# ccd_driver.net
KiCad netlist of a schematic drawn in EAGLE
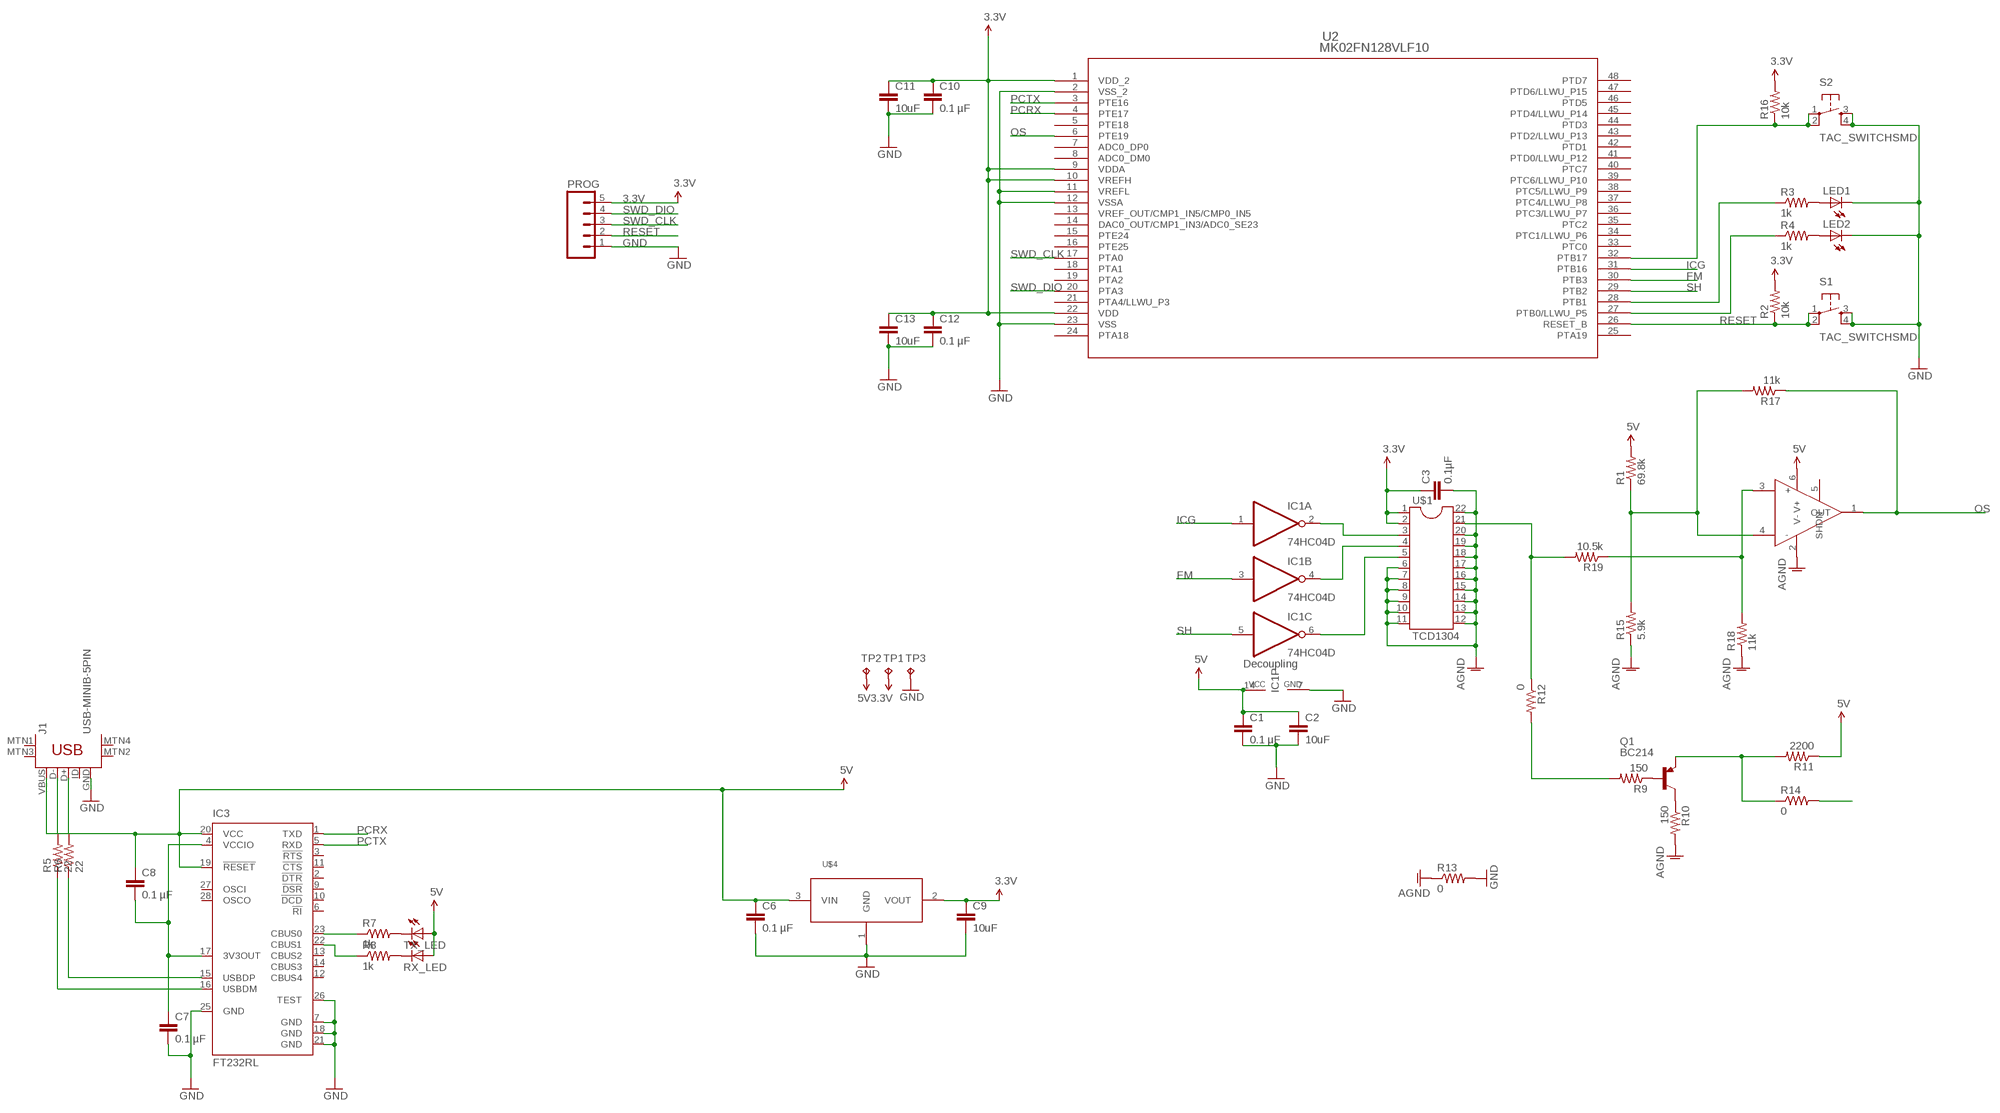
[diagram p0: schematic, sheet 1]

(export (version "E")
  (design (tool "Eeschema 10.0.6"))
  (components
    (comp (ref "C1")
      (value "0.1 µF")
      (footprint "eagle-import:C1206")
      (libsource (lib "eagle-import") (part "C-EUC1206"))
    )
    (comp (ref "C2")
      (value "10uF")
      (footprint "eagle-import:C1206")
      (libsource (lib "eagle-import") (part "C-EUC1206"))
    )
    (comp (ref "C3")
      (value "0.1µF")
      (footprint "eagle-import:C1206")
      (libsource (lib "eagle-import") (part "C-EUC1206"))
    )
    (comp (ref "C6")
      (value "0.1 µF")
      (footprint "eagle-import:C1206")
      (libsource (lib "eagle-import") (part "C-EUC1206"))
    )
    (comp (ref "C7")
      (value "0.1 µF")
      (footprint "eagle-import:C1206")
      (libsource (lib "eagle-import") (part "C-EUC1206"))
    )
    (comp (ref "C8")
      (value "0.1 µF")
      (footprint "eagle-import:C1206")
      (libsource (lib "eagle-import") (part "C-EUC1206"))
    )
    (comp (ref "C9")
      (value "10uF")
      (footprint "eagle-import:C1206")
      (libsource (lib "eagle-import") (part "C-EUC1206"))
    )
    (comp (ref "C10")
      (value "0.1 µF")
      (footprint "eagle-import:C1206")
      (libsource (lib "eagle-import") (part "C-EUC1206"))
    )
    (comp (ref "C11")
      (value "10uF")
      (footprint "eagle-import:C1206")
      (libsource (lib "eagle-import") (part "C-EUC1206"))
    )
    (comp (ref "C12")
      (value "0.1 µF")
      (footprint "eagle-import:C1206")
      (libsource (lib "eagle-import") (part "C-EUC1206"))
    )
    (comp (ref "C13")
      (value "10uF")
      (footprint "eagle-import:C1206")
      (libsource (lib "eagle-import") (part "C-EUC1206"))
    )
    (comp (ref "IC1")
      (value "74HC04D")
      (footprint "eagle-import:SO14")
      (libsource (lib "eagle-import") (part "7404DHC"))
    )
    (comp (ref "IC3")
      (value "FT232RL")
      (footprint "eagle-import:SSOP28")
      (libsource (lib "eagle-import") (part "FT232RL"))
    )
    (comp (ref "J1")
      (value "USB-MINIB-5PIN")
      (footprint "eagle-import:USB-MINIB")
      (libsource (lib "eagle-import") (part "USB-MINIB-5PIN"))
    )
    (comp (ref "LED1")
      (value "LEDCHIPLED_0805")
      (footprint "eagle-import:CHIPLED_0805")
      (libsource (lib "eagle-import") (part "LEDCHIPLED_0805"))
    )
    (comp (ref "LED2")
      (value "LEDCHIPLED_0805")
      (footprint "eagle-import:CHIPLED_0805")
      (libsource (lib "eagle-import") (part "LEDCHIPLED_0805"))
    )
    (comp (ref "PROG")
      (value "M05LOCK")
      (footprint "eagle-import:1X05_LOCK")
      (libsource (lib "eagle-import") (part "M05LOCK"))
    )
    (comp (ref "Q1")
      (value "BC214")
      (footprint "eagle-import:TO92")
      (libsource (lib "eagle-import") (part "BC214"))
    )
    (comp (ref "R1")
      (value "69.8k")
      (footprint "eagle-import:R0805")
      (libsource (lib "eagle-import") (part "R-US_R0805"))
    )
    (comp (ref "R2")
      (value "10k")
      (footprint "eagle-import:R0805")
      (libsource (lib "eagle-import") (part "R-US_R0805"))
    )
    (comp (ref "R3")
      (value "1k")
      (footprint "eagle-import:R0805")
      (libsource (lib "eagle-import") (part "R-US_R0805"))
    )
    (comp (ref "R4")
      (value "1k")
      (footprint "eagle-import:R0805")
      (libsource (lib "eagle-import") (part "R-US_R0805"))
    )
    (comp (ref "R5")
      (value "22")
      (footprint "eagle-import:R0805")
      (libsource (lib "eagle-import") (part "R-US_R0805"))
    )
    (comp (ref "R6")
      (value "22")
      (footprint "eagle-import:R0805")
      (libsource (lib "eagle-import") (part "R-US_R0805"))
    )
    (comp (ref "R7")
      (value "1k")
      (footprint "eagle-import:R0805")
      (libsource (lib "eagle-import") (part "R-US_R0805"))
    )
    (comp (ref "R8")
      (value "1k")
      (footprint "eagle-import:R0805")
      (libsource (lib "eagle-import") (part "R-US_R0805"))
    )
    (comp (ref "R9")
      (value "150")
      (footprint "eagle-import:R0805")
      (libsource (lib "eagle-import") (part "R-US_R0805"))
    )
    (comp (ref "R10")
      (value "150")
      (footprint "eagle-import:R0805")
      (libsource (lib "eagle-import") (part "R-US_R0805"))
    )
    (comp (ref "R11")
      (value "2200")
      (footprint "eagle-import:R0805")
      (libsource (lib "eagle-import") (part "R-US_R0805"))
    )
    (comp (ref "R12")
      (value "0")
      (footprint "eagle-import:R0805")
      (libsource (lib "eagle-import") (part "R-US_R0805"))
    )
    (comp (ref "R13")
      (value "0")
      (footprint "eagle-import:R0805")
      (libsource (lib "eagle-import") (part "R-US_R0805"))
    )
    (comp (ref "R14")
      (value "0")
      (footprint "eagle-import:R0805")
      (libsource (lib "eagle-import") (part "R-US_R0805"))
    )
    (comp (ref "R15")
      (value "5.9k")
      (footprint "eagle-import:R0805")
      (libsource (lib "eagle-import") (part "R-US_R0805"))
    )
    (comp (ref "R16")
      (value "10k")
      (footprint "eagle-import:R0805")
      (libsource (lib "eagle-import") (part "R-US_R0805"))
    )
    (comp (ref "R17")
      (value "11k")
      (footprint "eagle-import:R0805")
      (libsource (lib "eagle-import") (part "R-US_R0805"))
    )
    (comp (ref "R18")
      (value "11k")
      (footprint "eagle-import:R0805")
      (libsource (lib "eagle-import") (part "R-US_R0805"))
    )
    (comp (ref "R19")
      (value "10.5k")
      (footprint "eagle-import:R0805")
      (libsource (lib "eagle-import") (part "R-US_R0805"))
    )
    (comp (ref "RX_LED")
      (value "LEDCHIPLED_0805")
      (footprint "eagle-import:CHIPLED_0805")
      (libsource (lib "eagle-import") (part "LEDCHIPLED_0805"))
    )
    (comp (ref "S1")
      (value "TAC_SWITCHSMD")
      (footprint "eagle-import:TACTILE-SWITCH-SMD")
      (libsource (lib "eagle-import") (part "TAC_SWITCHSMD"))
    )
    (comp (ref "S2")
      (value "TAC_SWITCHSMD")
      (footprint "eagle-import:TACTILE-SWITCH-SMD")
      (libsource (lib "eagle-import") (part "TAC_SWITCHSMD"))
    )
    (comp (ref "TP1")
      (value "TPPAD1-17Y")
      (footprint "eagle-import:P1-17Y")
      (libsource (lib "eagle-import") (part "TPPAD1-17Y"))
    )
    (comp (ref "TP2")
      (value "TPPAD1-17Y")
      (footprint "eagle-import:P1-17Y")
      (libsource (lib "eagle-import") (part "TPPAD1-17Y"))
    )
    (comp (ref "TP3")
      (value "TPPAD1-17Y")
      (footprint "eagle-import:P1-17Y")
      (libsource (lib "eagle-import") (part "TPPAD1-17Y"))
    )
    (comp (ref "TX_LED")
      (value "LEDCHIPLED_0805")
      (footprint "eagle-import:CHIPLED_0805")
      (libsource (lib "eagle-import") (part "LEDCHIPLED_0805"))
    )
    (comp (ref "U$1")
      (value "TCD1304")
      (footprint "eagle-import:TCD1304")
      (libsource (lib "eagle-import") (part "TCD1304"))
    )
    (comp (ref "U$3")
      (value "LTC6252")
      (footprint "eagle-import:TSOT23-6")
      (libsource (lib "eagle-import") (part "LTC6252"))
    )
    (comp (ref "U$4")
      (value "LD1117V33")
      (footprint "eagle-import:TO220H")
      (libsource (lib "eagle-import") (part "LD1117V33"))
    )
    (comp (ref "U2")
      (value "MK02FN128VLF10")
      (footprint "eagle-import:LQFP-48_7X7X1.6")
      (fields (field (name "MANUFACTURER_PART_NUMBER") "mk02fn128vlf10"))
      (libsource (lib "eagle-import") (part "MK02FN128VLF10"))
    )
  )
  (nets
    (net (code "1") (name "/FM") (class "Default")
      (node (ref "IC1") (pin "3") (pinfunction "I_3") (pintype "input"))
      (node (ref "U2") (pin "30") (pinfunction "PTB3_30") (pintype "bidirectional"))
    )
    (net (code "2") (name "/ICG") (class "Default")
      (node (ref "IC1") (pin "1") (pinfunction "I_1") (pintype "input"))
      (node (ref "U2") (pin "31") (pinfunction "PTB16_31") (pintype "bidirectional"))
    )
    (net (code "3") (name "/OS") (class "Default")
      (node (ref "R14") (pin "2") (pinfunction "2_2") (pintype "passive"))
      (node (ref "R17") (pin "1") (pinfunction "1_1") (pintype "passive"))
      (node (ref "U$3") (pin "1") (pinfunction "OUT_1") (pintype "bidirectional"))
      (node (ref "U2") (pin "6") (pinfunction "PTE19_6") (pintype "bidirectional"))
    )
    (net (code "4") (name "/PCRX") (class "Default")
      (node (ref "IC3") (pin "1") (pinfunction "TXD_1") (pintype "output"))
      (node (ref "U2") (pin "4") (pinfunction "PTE17_4") (pintype "bidirectional"))
    )
    (net (code "5") (name "/PCTX") (class "Default")
      (node (ref "IC3") (pin "5") (pinfunction "RXD_5") (pintype "input"))
      (node (ref "U2") (pin "3") (pinfunction "PTE16_3") (pintype "bidirectional"))
    )
    (net (code "6") (name "/RESET") (class "Default")
      (node (ref "PROG") (pin "2") (pinfunction "2_2") (pintype "passive"))
      (node (ref "R2") (pin "1") (pinfunction "1_1") (pintype "passive"))
      (node (ref "S1") (pin "1") (pinfunction "1_1") (pintype "passive"))
      (node (ref "S1") (pin "2") (pinfunction "2_2") (pintype "passive"))
      (node (ref "U2") (pin "26") (pinfunction "RESET_B_26") (pintype "passive"))
    )
    (net (code "7") (name "/SH") (class "Default")
      (node (ref "IC1") (pin "5") (pinfunction "I_5") (pintype "input"))
      (node (ref "U2") (pin "29") (pinfunction "PTB2_29") (pintype "bidirectional"))
    )
    (net (code "8") (name "/SWD_CLK") (class "Default")
      (node (ref "PROG") (pin "3") (pinfunction "3_3") (pintype "passive"))
      (node (ref "U2") (pin "17") (pinfunction "PTA0_17") (pintype "bidirectional"))
    )
    (net (code "9") (name "/SWD_DIO") (class "Default")
      (node (ref "PROG") (pin "4") (pinfunction "4_4") (pintype "passive"))
      (node (ref "U2") (pin "20") (pinfunction "PTA3_20") (pintype "bidirectional"))
    )
    (net (code "10") (name "3.3V") (class "Default")
      (node (ref "C10") (pin "1") (pinfunction "1_1") (pintype "passive"))
      (node (ref "C11") (pin "1") (pinfunction "1_1") (pintype "passive"))
      (node (ref "C12") (pin "1") (pinfunction "1_1") (pintype "passive"))
      (node (ref "C13") (pin "1") (pinfunction "1_1") (pintype "passive"))
      (node (ref "C3") (pin "1") (pinfunction "1_1") (pintype "passive"))
      (node (ref "C9") (pin "1") (pinfunction "1_1") (pintype "passive"))
      (node (ref "PROG") (pin "5") (pinfunction "5_5") (pintype "passive"))
      (node (ref "R16") (pin "2") (pinfunction "2_2") (pintype "passive"))
      (node (ref "R2") (pin "2") (pinfunction "2_2") (pintype "passive"))
      (node (ref "TP1") (pin "TP") (pinfunction "TP_TP") (pintype "input"))
      (node (ref "U$1") (pin "1") (pinfunction "1_1") (pintype "passive"))
      (node (ref "U$1") (pin "2") (pinfunction "2_2") (pintype "passive"))
      (node (ref "U$4") (pin "2") (pinfunction "VOUT_2") (pintype "bidirectional"))
      (node (ref "U2") (pin "1") (pinfunction "VDD_2_1") (pintype "power_in"))
      (node (ref "U2") (pin "10") (pinfunction "VREFH_10") (pintype "power_in"))
      (node (ref "U2") (pin "22") (pinfunction "VDD_22") (pintype "power_in"))
      (node (ref "U2") (pin "9") (pinfunction "VDDA_9") (pintype "power_in"))
    )
    (net (code "11") (name "5V") (class "Default")
      (node (ref "C1") (pin "1") (pinfunction "1_1") (pintype "passive"))
      (node (ref "C2") (pin "1") (pinfunction "1_1") (pintype "passive"))
      (node (ref "C6") (pin "1") (pinfunction "1_1") (pintype "passive"))
      (node (ref "C8") (pin "1") (pinfunction "1_1") (pintype "passive"))
      (node (ref "IC1") (pin "14") (pinfunction "VCC_14") (pintype "power_in"))
      (node (ref "IC3") (pin "19") (pinfunction "~{RESET}_19") (pintype "input"))
      (node (ref "IC3") (pin "20") (pinfunction "VCC_20") (pintype "power_in"))
      (node (ref "J1") (pin "VBUS") (pinfunction "VBUS_VBUS") (pintype "bidirectional"))
      (node (ref "R1") (pin "2") (pinfunction "2_2") (pintype "passive"))
      (node (ref "R11") (pin "1") (pinfunction "1_1") (pintype "passive"))
      (node (ref "RX_LED") (pin "A") (pinfunction "A_A") (pintype "passive"))
      (node (ref "TP2") (pin "TP") (pinfunction "TP_TP") (pintype "input"))
      (node (ref "TX_LED") (pin "A") (pinfunction "A_A") (pintype "passive"))
      (node (ref "U$3") (pin "6") (pinfunction "V+_6") (pintype "bidirectional"))
      (node (ref "U$4") (pin "3") (pinfunction "VIN_3") (pintype "bidirectional"))
    )
    (net (code "12") (name "AGND") (class "Default")
      (node (ref "C3") (pin "2") (pinfunction "2_2") (pintype "passive"))
      (node (ref "R10") (pin "2") (pinfunction "2_2") (pintype "passive"))
      (node (ref "R13") (pin "1") (pinfunction "1_1") (pintype "passive"))
      (node (ref "R15") (pin "1") (pinfunction "1_1") (pintype "passive"))
      (node (ref "R18") (pin "1") (pinfunction "1_1") (pintype "passive"))
      (node (ref "U$1") (pin "10") (pinfunction "10_10") (pintype "passive"))
      (node (ref "U$1") (pin "11") (pinfunction "11_11") (pintype "passive"))
      (node (ref "U$1") (pin "12") (pinfunction "12_12") (pintype "passive"))
      (node (ref "U$1") (pin "13") (pinfunction "13_13") (pintype "passive"))
      (node (ref "U$1") (pin "14") (pinfunction "14_14") (pintype "passive"))
      (node (ref "U$1") (pin "15") (pinfunction "15_15") (pintype "passive"))
      (node (ref "U$1") (pin "16") (pinfunction "16_16") (pintype "passive"))
      (node (ref "U$1") (pin "17") (pinfunction "17_17") (pintype "passive"))
      (node (ref "U$1") (pin "18") (pinfunction "18_18") (pintype "passive"))
      (node (ref "U$1") (pin "19") (pinfunction "19_19") (pintype "passive"))
      (node (ref "U$1") (pin "20") (pinfunction "20_20") (pintype "passive"))
      (node (ref "U$1") (pin "22") (pinfunction "22_22") (pintype "passive"))
      (node (ref "U$1") (pin "6") (pinfunction "6_6") (pintype "passive"))
      (node (ref "U$1") (pin "7") (pinfunction "7_7") (pintype "passive"))
      (node (ref "U$1") (pin "8") (pinfunction "8_8") (pintype "passive"))
      (node (ref "U$1") (pin "9") (pinfunction "9_9") (pintype "passive"))
      (node (ref "U$3") (pin "2") (pinfunction "V-_2") (pintype "bidirectional"))
    )
    (net (code "13") (name "GND") (class "Default")
      (node (ref "C1") (pin "2") (pinfunction "2_2") (pintype "passive"))
      (node (ref "C10") (pin "2") (pinfunction "2_2") (pintype "passive"))
      (node (ref "C11") (pin "2") (pinfunction "2_2") (pintype "passive"))
      (node (ref "C12") (pin "2") (pinfunction "2_2") (pintype "passive"))
      (node (ref "C13") (pin "2") (pinfunction "2_2") (pintype "passive"))
      (node (ref "C2") (pin "2") (pinfunction "2_2") (pintype "passive"))
      (node (ref "C6") (pin "2") (pinfunction "2_2") (pintype "passive"))
      (node (ref "C7") (pin "2") (pinfunction "2_2") (pintype "passive"))
      (node (ref "C9") (pin "2") (pinfunction "2_2") (pintype "passive"))
      (node (ref "IC1") (pin "7") (pinfunction "GND_7") (pintype "power_in"))
      (node (ref "IC3") (pin "18") (pinfunction "GND_18") (pintype "power_in"))
      (node (ref "IC3") (pin "21") (pinfunction "GND_21") (pintype "power_in"))
      (node (ref "IC3") (pin "25") (pinfunction "GND_25") (pintype "power_in"))
      (node (ref "IC3") (pin "26") (pinfunction "TEST_26") (pintype "input"))
      (node (ref "IC3") (pin "7") (pinfunction "GND_7") (pintype "power_in"))
      (node (ref "J1") (pin "GND") (pinfunction "GND_GND") (pintype "bidirectional"))
      (node (ref "LED1") (pin "C") (pinfunction "C_C") (pintype "passive"))
      (node (ref "LED2") (pin "C") (pinfunction "C_C") (pintype "passive"))
      (node (ref "PROG") (pin "1") (pinfunction "1_1") (pintype "passive"))
      (node (ref "R13") (pin "2") (pinfunction "2_2") (pintype "passive"))
      (node (ref "S1") (pin "3") (pinfunction "3_3") (pintype "passive"))
      (node (ref "S1") (pin "4") (pinfunction "4_4") (pintype "passive"))
      (node (ref "S2") (pin "3") (pinfunction "3_3") (pintype "passive"))
      (node (ref "S2") (pin "4") (pinfunction "4_4") (pintype "passive"))
      (node (ref "TP3") (pin "TP") (pinfunction "TP_TP") (pintype "input"))
      (node (ref "U$4") (pin "1") (pinfunction "GND_1") (pintype "bidirectional"))
      (node (ref "U2") (pin "11") (pinfunction "VREFL_11") (pintype "power_in"))
      (node (ref "U2") (pin "12") (pinfunction "VSSA_12") (pintype "power_in"))
      (node (ref "U2") (pin "2") (pinfunction "VSS_2_2") (pintype "power_in"))
      (node (ref "U2") (pin "23") (pinfunction "VSS_23") (pintype "power_in"))
    )
    (net (code "14") (name "Net-(IC1A-O)") (class "Default")
      (node (ref "IC1") (pin "2") (pinfunction "O_2") (pintype "output"))
      (node (ref "U$1") (pin "3") (pinfunction "3_3") (pintype "passive"))
    )
    (net (code "15") (name "Net-(IC1B-O)") (class "Default")
      (node (ref "IC1") (pin "4") (pinfunction "O_4") (pintype "output"))
      (node (ref "U$1") (pin "4") (pinfunction "4_4") (pintype "passive"))
    )
    (net (code "16") (name "Net-(IC1C-O)") (class "Default")
      (node (ref "IC1") (pin "6") (pinfunction "O_6") (pintype "output"))
      (node (ref "U$1") (pin "5") (pinfunction "5_5") (pintype "passive"))
    )
    (net (code "17") (name "Net-(IC3-3V3OUT)") (class "Default")
      (node (ref "C7") (pin "1") (pinfunction "1_1") (pintype "passive"))
      (node (ref "C8") (pin "2") (pinfunction "2_2") (pintype "passive"))
      (node (ref "IC3") (pin "17") (pinfunction "3V3OUT_17") (pintype "output"))
      (node (ref "IC3") (pin "4") (pinfunction "VCCIO_4") (pintype "power_in"))
    )
    (net (code "18") (name "Net-(IC3-CBUS0)") (class "Default")
      (node (ref "IC3") (pin "23") (pinfunction "CBUS0_23") (pintype "bidirectional"))
      (node (ref "R7") (pin "1") (pinfunction "1_1") (pintype "passive"))
    )
    (net (code "19") (name "Net-(IC3-CBUS1)") (class "Default")
      (node (ref "IC3") (pin "22") (pinfunction "CBUS1_22") (pintype "bidirectional"))
      (node (ref "R8") (pin "1") (pinfunction "1_1") (pintype "passive"))
    )
    (net (code "20") (name "Net-(IC3-USBDM)") (class "Default")
      (node (ref "IC3") (pin "16") (pinfunction "USBDM_16") (pintype "bidirectional"))
      (node (ref "R5") (pin "1") (pinfunction "1_1") (pintype "passive"))
    )
    (net (code "21") (name "Net-(IC3-USBDP)") (class "Default")
      (node (ref "IC3") (pin "15") (pinfunction "USBDP_15") (pintype "bidirectional"))
      (node (ref "R6") (pin "1") (pinfunction "1_1") (pintype "passive"))
    )
    (net (code "22") (name "Net-(J1-PadD+)") (class "Default")
      (node (ref "J1") (pin "D+") (pinfunction "D+_D+") (pintype "bidirectional"))
      (node (ref "R6") (pin "2") (pinfunction "2_2") (pintype "passive"))
    )
    (net (code "23") (name "Net-(J1-PadD-)") (class "Default")
      (node (ref "J1") (pin "D-") (pinfunction "D-_D-") (pintype "bidirectional"))
      (node (ref "R5") (pin "2") (pinfunction "2_2") (pintype "passive"))
    )
    (net (code "24") (name "Net-(LED1-PadA)") (class "Default")
      (node (ref "LED1") (pin "A") (pinfunction "A_A") (pintype "passive"))
      (node (ref "R3") (pin "2") (pinfunction "2_2") (pintype "passive"))
    )
    (net (code "25") (name "Net-(LED2-PadA)") (class "Default")
      (node (ref "LED2") (pin "A") (pinfunction "A_A") (pintype "passive"))
      (node (ref "R4") (pin "2") (pinfunction "2_2") (pintype "passive"))
    )
    (net (code "26") (name "Net-(Q1-B)") (class "Default")
      (node (ref "Q1") (pin "2") (pinfunction "B_2") (pintype "passive"))
      (node (ref "R9") (pin "1") (pinfunction "1_1") (pintype "passive"))
    )
    (net (code "27") (name "Net-(Q1-C)") (class "Default")
      (node (ref "Q1") (pin "3") (pinfunction "C_3") (pintype "passive"))
      (node (ref "R10") (pin "1") (pinfunction "1_1") (pintype "passive"))
    )
    (net (code "28") (name "Net-(Q1-E)") (class "Default")
      (node (ref "Q1") (pin "1") (pinfunction "E_1") (pintype "passive"))
      (node (ref "R11") (pin "2") (pinfunction "2_2") (pintype "passive"))
      (node (ref "R14") (pin "1") (pinfunction "1_1") (pintype "passive"))
    )
    (net (code "29") (name "Net-(R7-Pad2)") (class "Default")
      (node (ref "R7") (pin "2") (pinfunction "2_2") (pintype "passive"))
      (node (ref "TX_LED") (pin "C") (pinfunction "C_C") (pintype "passive"))
    )
    (net (code "30") (name "Net-(R8-Pad2)") (class "Default")
      (node (ref "R8") (pin "2") (pinfunction "2_2") (pintype "passive"))
      (node (ref "RX_LED") (pin "C") (pinfunction "C_C") (pintype "passive"))
    )
    (net (code "31") (name "Net-(R12-Pad1)") (class "Default")
      (node (ref "R12") (pin "1") (pinfunction "1_1") (pintype "passive"))
      (node (ref "R19") (pin "2") (pinfunction "2_2") (pintype "passive"))
      (node (ref "U$1") (pin "21") (pinfunction "21_21") (pintype "passive"))
    )
    (net (code "32") (name "Net-(R12-Pad2)") (class "Default")
      (node (ref "R12") (pin "2") (pinfunction "2_2") (pintype "passive"))
      (node (ref "R9") (pin "2") (pinfunction "2_2") (pintype "passive"))
    )
    (net (code "33") (name "Net-(U$3-+)") (class "Default")
      (node (ref "R18") (pin "2") (pinfunction "2_2") (pintype "passive"))
      (node (ref "R19") (pin "1") (pinfunction "1_1") (pintype "passive"))
      (node (ref "U$3") (pin "3") (pinfunction "+_3") (pintype "bidirectional"))
    )
    (net (code "34") (name "Net-(U$3--)") (class "Default")
      (node (ref "R1") (pin "1") (pinfunction "1_1") (pintype "passive"))
      (node (ref "R15") (pin "2") (pinfunction "2_2") (pintype "passive"))
      (node (ref "R17") (pin "2") (pinfunction "2_2") (pintype "passive"))
      (node (ref "U$3") (pin "4") (pinfunction "-_4") (pintype "bidirectional"))
    )
    (net (code "35") (name "Net-(U2-PTB0{slash}LLWU_P5)") (class "Default")
      (node (ref "R4") (pin "1") (pinfunction "1_1") (pintype "passive"))
      (node (ref "U2") (pin "27") (pinfunction "PTB0/LLWU_P5_27") (pintype "bidirectional"))
    )
    (net (code "36") (name "Net-(U2-PTB1)") (class "Default")
      (node (ref "R3") (pin "1") (pinfunction "1_1") (pintype "passive"))
      (node (ref "U2") (pin "28") (pinfunction "PTB1_28") (pintype "bidirectional"))
    )
    (net (code "37") (name "Net-(U2-PTB17)") (class "Default")
      (node (ref "R16") (pin "1") (pinfunction "1_1") (pintype "passive"))
      (node (ref "S2") (pin "1") (pinfunction "1_1") (pintype "passive"))
      (node (ref "S2") (pin "2") (pinfunction "2_2") (pintype "passive"))
      (node (ref "U2") (pin "32") (pinfunction "PTB17_32") (pintype "bidirectional"))
    )
    (net (code "38") (name "unconnected-(IC3-CBUS2-Pad13)") (class "Default")
      (node (ref "IC3") (pin "13") (pinfunction "CBUS2_13") (pintype "bidirectional"))
    )
    (net (code "39") (name "unconnected-(IC3-CBUS3-Pad14)") (class "Default")
      (node (ref "IC3") (pin "14") (pinfunction "CBUS3_14") (pintype "bidirectional"))
    )
    (net (code "40") (name "unconnected-(IC3-CBUS4-Pad12)") (class "Default")
      (node (ref "IC3") (pin "12") (pinfunction "CBUS4_12") (pintype "bidirectional"))
    )
    (net (code "41") (name "unconnected-(IC3-OSCI-Pad27)") (class "Default")
      (node (ref "IC3") (pin "27") (pinfunction "OSCI_27") (pintype "input"))
    )
    (net (code "42") (name "unconnected-(IC3-OSCO-Pad28)") (class "Default")
      (node (ref "IC3") (pin "28") (pinfunction "OSCO_28") (pintype "output"))
    )
    (net (code "43") (name "unconnected-(IC3-~{CTS}-Pad11)") (class "Default")
      (node (ref "IC3") (pin "11") (pinfunction "~{CTS}_11") (pintype "input"))
    )
    (net (code "44") (name "unconnected-(IC3-~{DCD}-Pad10)") (class "Default")
      (node (ref "IC3") (pin "10") (pinfunction "~{DCD}_10") (pintype "input"))
    )
    (net (code "45") (name "unconnected-(IC3-~{DSR}-Pad9)") (class "Default")
      (node (ref "IC3") (pin "9") (pinfunction "~{DSR}_9") (pintype "input"))
    )
    (net (code "46") (name "unconnected-(IC3-~{DTR}-Pad2)") (class "Default")
      (node (ref "IC3") (pin "2") (pinfunction "~{DTR}_2") (pintype "output"))
    )
    (net (code "47") (name "unconnected-(IC3-~{RI}-Pad6)") (class "Default")
      (node (ref "IC3") (pin "6") (pinfunction "~{RI}_6") (pintype "input"))
    )
    (net (code "48") (name "unconnected-(IC3-~{RTS}-Pad3)") (class "Default")
      (node (ref "IC3") (pin "3") (pinfunction "~{RTS}_3") (pintype "output"))
    )
    (net (code "49") (name "unconnected-(J1-MTN1-PadMTN3)") (class "Default")
      (node (ref "J1") (pin "MTN3") (pinfunction "MTN1_MTN3") (pintype "bidirectional"))
    )
    (net (code "50") (name "unconnected-(J1-MTN2-PadMTN1)") (class "Default")
      (node (ref "J1") (pin "MTN1") (pinfunction "MTN2_MTN1") (pintype "bidirectional"))
    )
    (net (code "51") (name "unconnected-(J1-MTN3-PadMTN2)") (class "Default")
      (node (ref "J1") (pin "MTN2") (pinfunction "MTN3_MTN2") (pintype "bidirectional"))
    )
    (net (code "52") (name "unconnected-(J1-PadID)") (class "Default")
      (node (ref "J1") (pin "ID") (pinfunction "ID_ID") (pintype "bidirectional"))
    )
    (net (code "53") (name "unconnected-(J1-PadMTN4)") (class "Default")
      (node (ref "J1") (pin "MTN4") (pinfunction "MTN4_MTN4") (pintype "bidirectional"))
    )
    (net (code "54") (name "unconnected-(U$3-SHDN-Pad5)") (class "Default")
      (node (ref "U$3") (pin "5") (pinfunction "SHDN_5") (pintype "bidirectional"))
    )
    (net (code "55") (name "unconnected-(U2-ADC0_DM0-Pad8)") (class "Default")
      (node (ref "U2") (pin "8") (pinfunction "ADC0_DM0_8") (pintype "bidirectional"))
    )
    (net (code "56") (name "unconnected-(U2-ADC0_DP0-Pad7)") (class "Default")
      (node (ref "U2") (pin "7") (pinfunction "ADC0_DP0_7") (pintype "bidirectional"))
    )
    (net (code "57") (name "unconnected-(U2-DAC0_OUT{slash}CMP1_IN3{slash}ADC0_SE23-Pad14)") (class "Default")
      (node (ref "U2") (pin "14") (pinfunction "DAC0_OUT/CMP1_IN3/ADC0_SE23_14") (pintype "bidirectional"))
    )
    (net (code "58") (name "unconnected-(U2-PTA1-Pad18)") (class "Default")
      (node (ref "U2") (pin "18") (pinfunction "PTA1_18") (pintype "bidirectional"))
    )
    (net (code "59") (name "unconnected-(U2-PTA2-Pad19)") (class "Default")
      (node (ref "U2") (pin "19") (pinfunction "PTA2_19") (pintype "bidirectional"))
    )
    (net (code "60") (name "unconnected-(U2-PTA4{slash}LLWU_P3-Pad21)") (class "Default")
      (node (ref "U2") (pin "21") (pinfunction "PTA4/LLWU_P3_21") (pintype "bidirectional"))
    )
    (net (code "61") (name "unconnected-(U2-PTA18-Pad24)") (class "Default")
      (node (ref "U2") (pin "24") (pinfunction "PTA18_24") (pintype "bidirectional"))
    )
    (net (code "62") (name "unconnected-(U2-PTA19-Pad25)") (class "Default")
      (node (ref "U2") (pin "25") (pinfunction "PTA19_25") (pintype "bidirectional"))
    )
    (net (code "63") (name "unconnected-(U2-PTC0-Pad33)") (class "Default")
      (node (ref "U2") (pin "33") (pinfunction "PTC0_33") (pintype "bidirectional"))
    )
    (net (code "64") (name "unconnected-(U2-PTC1{slash}LLWU_P6-Pad34)") (class "Default")
      (node (ref "U2") (pin "34") (pinfunction "PTC1/LLWU_P6_34") (pintype "bidirectional"))
    )
    (net (code "65") (name "unconnected-(U2-PTC2-Pad35)") (class "Default")
      (node (ref "U2") (pin "35") (pinfunction "PTC2_35") (pintype "bidirectional"))
    )
    (net (code "66") (name "unconnected-(U2-PTC3{slash}LLWU_P7-Pad36)") (class "Default")
      (node (ref "U2") (pin "36") (pinfunction "PTC3/LLWU_P7_36") (pintype "bidirectional"))
    )
    (net (code "67") (name "unconnected-(U2-PTC4{slash}LLWU_P8-Pad37)") (class "Default")
      (node (ref "U2") (pin "37") (pinfunction "PTC4/LLWU_P8_37") (pintype "bidirectional"))
    )
    (net (code "68") (name "unconnected-(U2-PTC5{slash}LLWU_P9-Pad38)") (class "Default")
      (node (ref "U2") (pin "38") (pinfunction "PTC5/LLWU_P9_38") (pintype "bidirectional"))
    )
    (net (code "69") (name "unconnected-(U2-PTC6{slash}LLWU_P10-Pad39)") (class "Default")
      (node (ref "U2") (pin "39") (pinfunction "PTC6/LLWU_P10_39") (pintype "bidirectional"))
    )
    (net (code "70") (name "unconnected-(U2-PTC7-Pad40)") (class "Default")
      (node (ref "U2") (pin "40") (pinfunction "PTC7_40") (pintype "bidirectional"))
    )
    (net (code "71") (name "unconnected-(U2-PTD0{slash}LLWU_P12-Pad41)") (class "Default")
      (node (ref "U2") (pin "41") (pinfunction "PTD0/LLWU_P12_41") (pintype "bidirectional"))
    )
    (net (code "72") (name "unconnected-(U2-PTD1-Pad42)") (class "Default")
      (node (ref "U2") (pin "42") (pinfunction "PTD1_42") (pintype "bidirectional"))
    )
    (net (code "73") (name "unconnected-(U2-PTD2{slash}LLWU_P13-Pad43)") (class "Default")
      (node (ref "U2") (pin "43") (pinfunction "PTD2/LLWU_P13_43") (pintype "bidirectional"))
    )
    (net (code "74") (name "unconnected-(U2-PTD3-Pad44)") (class "Default")
      (node (ref "U2") (pin "44") (pinfunction "PTD3_44") (pintype "bidirectional"))
    )
    (net (code "75") (name "unconnected-(U2-PTD4{slash}LLWU_P14-Pad45)") (class "Default")
      (node (ref "U2") (pin "45") (pinfunction "PTD4/LLWU_P14_45") (pintype "bidirectional"))
    )
    (net (code "76") (name "unconnected-(U2-PTD5-Pad46)") (class "Default")
      (node (ref "U2") (pin "46") (pinfunction "PTD5_46") (pintype "bidirectional"))
    )
    (net (code "77") (name "unconnected-(U2-PTD6{slash}LLWU_P15-Pad47)") (class "Default")
      (node (ref "U2") (pin "47") (pinfunction "PTD6/LLWU_P15_47") (pintype "bidirectional"))
    )
    (net (code "78") (name "unconnected-(U2-PTD7-Pad48)") (class "Default")
      (node (ref "U2") (pin "48") (pinfunction "PTD7_48") (pintype "bidirectional"))
    )
    (net (code "79") (name "unconnected-(U2-PTE18-Pad5)") (class "Default")
      (node (ref "U2") (pin "5") (pinfunction "PTE18_5") (pintype "bidirectional"))
    )
    (net (code "80") (name "unconnected-(U2-PTE24-Pad15)") (class "Default")
      (node (ref "U2") (pin "15") (pinfunction "PTE24_15") (pintype "bidirectional"))
    )
    (net (code "81") (name "unconnected-(U2-PTE25-Pad16)") (class "Default")
      (node (ref "U2") (pin "16") (pinfunction "PTE25_16") (pintype "bidirectional"))
    )
    (net (code "82") (name "unconnected-(U2-VREF_OUT{slash}CMP1_IN5{slash}CMP0_IN5-Pad13)") (class "Default")
      (node (ref "U2") (pin "13") (pinfunction "VREF_OUT/CMP1_IN5/CMP0_IN5_13") (pintype "bidirectional"))
    )
  )
)
